# Sheet1.net
KiCad netlist of a schematic drawn in Altium Designer
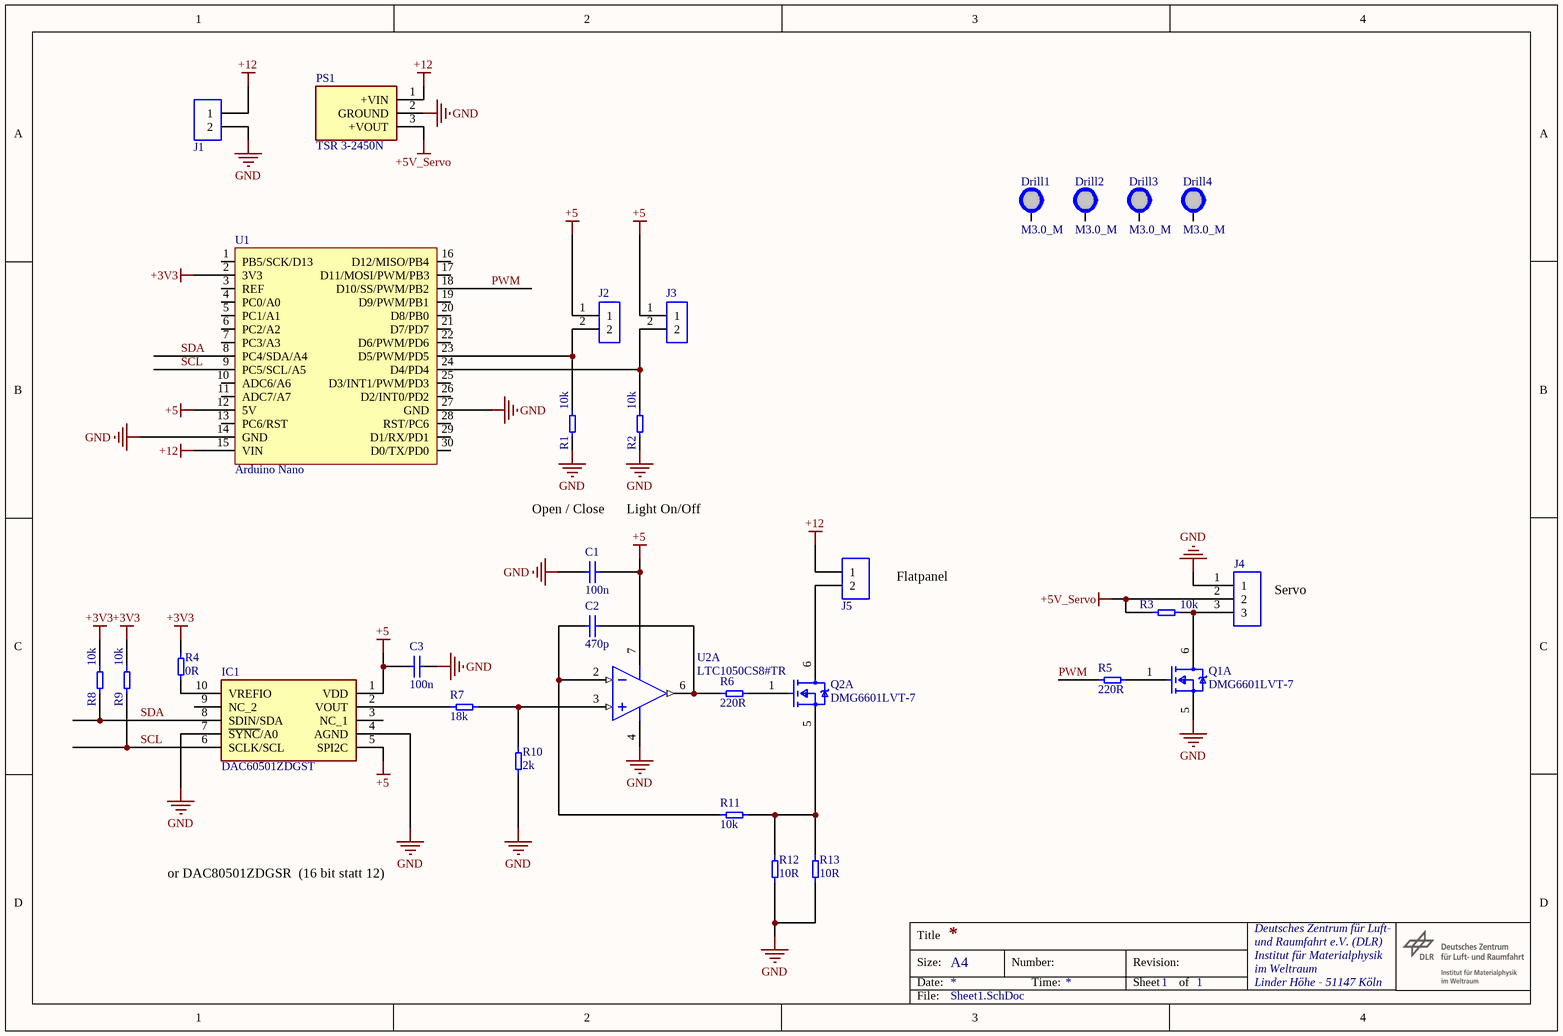
[diagram p0: Sheet1.SchDoc]

(export (version "E")
  (design (tool "Eeschema 10.0.6"))
  (components
    (comp (ref "C1")
      (value "100n")
      (footprint "C0603_L")
      (fields
        (field (name "PUBLISHER") "Altium Limited")
        (field (name ".CHECKED PCB") "RF")
        (field (name ".CHECKED SCH") "RF")
      )
      (libsource (lib "Passive Bauelemente") (part "C0603"))
    )
    (comp (ref "C2")
      (value "470p")
      (footprint "C0603_L")
      (fields
        (field (name "PUBLISHER") "Altium Limited")
        (field (name ".CHECKED PCB") "RF")
        (field (name ".CHECKED SCH") "RF")
      )
      (libsource (lib "Passive Bauelemente") (part "C0603"))
    )
    (comp (ref "C3")
      (value "100n")
      (footprint "C0603_L")
      (fields
        (field (name "PUBLISHER") "Altium Limited")
        (field (name ".CHECKED PCB") "RF")
        (field (name ".CHECKED SCH") "RF")
      )
      (libsource (lib "Passive Bauelemente") (part "C0603"))
    )
    (comp (ref "Drill1")
      (value "M3.0_M")
      (footprint "M3.0_M")
      (fields (field (name ".CHECKED PCB") "RF") (field (name ".CHECKED SCH") "RF"))
      (libsource (lib "Drills") (part "Drill"))
    )
    (comp (ref "Drill2")
      (value "M3.0_M")
      (footprint "M3.0_M")
      (fields (field (name ".CHECKED PCB") "RF") (field (name ".CHECKED SCH") "RF"))
      (libsource (lib "Drills") (part "Drill"))
    )
    (comp (ref "Drill3")
      (value "M3.0_M")
      (footprint "M3.0_M")
      (fields (field (name ".CHECKED PCB") "RF") (field (name ".CHECKED SCH") "RF"))
      (libsource (lib "Drills") (part "Drill"))
    )
    (comp (ref "Drill4")
      (value "M3.0_M")
      (footprint "M3.0_M")
      (fields (field (name ".CHECKED PCB") "RF") (field (name ".CHECKED SCH") "RF"))
      (libsource (lib "Drills") (part "Drill"))
    )
    (comp (ref "IC1")
      (value "DAC60501ZDGST")
      (footprint "SamacSys:SOP50P490X110-10N")
      (description "Integrated Circuit")
      (fields (field (name "MOUSER PART NUMBER") "595-DAC60501ZDGST"))
      (libsource (lib "*") (part "DAC60501ZDGST"))
    )
    (comp (ref "J1")
      (value "PM_5.08_3_90_3.5_SW_-176052000")
      (footprint "MKDSN 5,08/2 2,5")
      (description "间距5.08mm 2pin 10A 300V 可拼接 螺钉式 直插 配线24-14AWG(0.2-2.5)mm²")
      (fields
        (field (name "MANUFACTURER") "Phoenix Contact")
        (field (name "MANUFACTURER PART NUMBER") "1888687")
        (field (name ".CHECKED PCB") "PS")
        (field (name ".CHECKED SCH") "PS")
      )
      (libsource (lib "Phoenix Contact") (part "MKDSN 5,08/2 2,5"))
    )
    (comp (ref "J2")
      (value "896-7620")
      (footprint "2P Stiftleiste 2,54 mm")
      (fields
        (field (name "MANUFACTURER_PART_NUMBER") "42375-0002")
        (field (name ".CHECKED PCB") "RF")
        (field (name ".CHECKED SCH") "RF")
      )
      (libsource (lib "EigenDefault") (part "2P Stiftleiste 2,54"))
    )
    (comp (ref "J3")
      (value "896-7620")
      (footprint "2P Stiftleiste 2,54 mm")
      (fields
        (field (name "MANUFACTURER_PART_NUMBER") "42375-0002")
        (field (name ".CHECKED PCB") "RF")
        (field (name ".CHECKED SCH") "RF")
      )
      (libsource (lib "EigenDefault") (part "2P Stiftleiste 2,54"))
    )
    (comp (ref "J4")
      (value "251-8092")
      (footprint "3P Stiftleiste 2,54 mm")
      (fields (field (name ".CHECKED PCB") "RF") (field (name ".CHECKED SCH") "RF"))
      (libsource (lib "EigenDefault") (part "3P Stiftleiste 2,54"))
    )
    (comp (ref "J5")
      (value "PM_5.08_3_90_3.5_SW_-176052000")
      (footprint "MKDSN 5,08/2 2,5")
      (description "间距5.08mm 2pin 10A 300V 可拼接 螺钉式 直插 配线24-14AWG(0.2-2.5)mm²")
      (fields
        (field (name "MANUFACTURER") "Phoenix Contact")
        (field (name "MANUFACTURER PART NUMBER") "1888687")
        (field (name ".CHECKED PCB") "PS")
        (field (name ".CHECKED SCH") "PS")
      )
      (libsource (lib "Phoenix Contact") (part "MKDSN 5,08/2 2,5"))
    )
    (comp (ref "PS1")
      (value "TSR 3-2450N")
      (footprint "SamacSys:TSR324120N")
      (description "or TSR 3-2450N")
      (libsource (lib "*") (part "TSR_3-24120N"))
    )
    (comp (ref "Q1")
      (value "DMG6601LVT-7")
      (footprint "FP-TSOT26-MFG")
      (description "MOSFET N/P-CH 30V 26TSOT")
      (fields
        (field (name "OCTOPART") "https://octopart.com/dmg6601lvt-7-diodes+inc.-24548281")
        (field (name "MANUFACTURER") "Diodes Inc.")
      )
      (libsource (lib "Altium Content Vault") (part "06fe37a93ab8884fb11e636f76dd7e0"))
    )
    (comp (ref "Q2")
      (value "DMG6601LVT-7")
      (footprint "FP-TSOT26-MFG")
      (description "MOSFET N/P-CH 30V 26TSOT")
      (fields
        (field (name "OCTOPART") "https://octopart.com/dmg6601lvt-7-diodes+inc.-24548281")
        (field (name "MANUFACTURER") "Diodes Inc.")
      )
      (libsource (lib "Altium Content Vault") (part "06fe37a93ab8884fb11e636f76dd7e0"))
    )
    (comp (ref "R1")
      (value "10k")
      (footprint "R0603_M")
      (fields
        (field (name "POWER") "35 W")
        (field (name "PUBLISHER") "Altium Limited")
        (field (name ".CHECKED PCB") "RF")
        (field (name ".CHECKED SCH") "RF")
      )
      (libsource (lib "Passive Bauelemente") (part "R0603"))
    )
    (comp (ref "R2")
      (value "10k")
      (footprint "R0603_M")
      (fields
        (field (name "POWER") "35 W")
        (field (name "PUBLISHER") "Altium Limited")
        (field (name ".CHECKED PCB") "RF")
        (field (name ".CHECKED SCH") "RF")
      )
      (libsource (lib "Passive Bauelemente") (part "R0603"))
    )
    (comp (ref "R3")
      (value "10k")
      (footprint "R0603_M")
      (fields
        (field (name "POWER") "35 W")
        (field (name "PUBLISHER") "Altium Limited")
        (field (name ".CHECKED PCB") "RF")
        (field (name ".CHECKED SCH") "RF")
      )
      (libsource (lib "Passive Bauelemente") (part "R0603"))
    )
    (comp (ref "R4")
      (value "0R")
      (footprint "R0603_M")
      (fields
        (field (name "POWER") "35 W")
        (field (name "PUBLISHER") "Altium Limited")
        (field (name ".CHECKED PCB") "RF")
        (field (name ".CHECKED SCH") "RF")
      )
      (libsource (lib "Passive Bauelemente") (part "R0603"))
    )
    (comp (ref "R5")
      (value "220R")
      (footprint "R0603_M")
      (fields
        (field (name "POWER") "35 W")
        (field (name "PUBLISHER") "Altium Limited")
        (field (name ".CHECKED PCB") "RF")
        (field (name ".CHECKED SCH") "RF")
      )
      (libsource (lib "Passive Bauelemente") (part "R0603"))
    )
    (comp (ref "R6")
      (value "220R")
      (footprint "R0603_M")
      (fields
        (field (name "POWER") "35 W")
        (field (name "PUBLISHER") "Altium Limited")
        (field (name ".CHECKED PCB") "RF")
        (field (name ".CHECKED SCH") "RF")
      )
      (libsource (lib "Passive Bauelemente") (part "R0603"))
    )
    (comp (ref "R7")
      (value "18k")
      (footprint "R0603_M")
      (fields
        (field (name "POWER") "35 W")
        (field (name "PUBLISHER") "Altium Limited")
        (field (name ".CHECKED PCB") "RF")
        (field (name ".CHECKED SCH") "RF")
      )
      (libsource (lib "Passive Bauelemente") (part "R0603"))
    )
    (comp (ref "R8")
      (value "10k")
      (footprint "R0603_M")
      (fields
        (field (name "POWER") "35 W")
        (field (name "PUBLISHER") "Altium Limited")
        (field (name ".CHECKED PCB") "RF")
        (field (name ".CHECKED SCH") "RF")
      )
      (libsource (lib "Passive Bauelemente") (part "R0603"))
    )
    (comp (ref "R9")
      (value "10k")
      (footprint "R0603_M")
      (fields
        (field (name "POWER") "35 W")
        (field (name "PUBLISHER") "Altium Limited")
        (field (name ".CHECKED PCB") "RF")
        (field (name ".CHECKED SCH") "RF")
      )
      (libsource (lib "Passive Bauelemente") (part "R0603"))
    )
    (comp (ref "R10")
      (value "2k")
      (footprint "R0603_M")
      (fields
        (field (name "POWER") "35 W")
        (field (name "PUBLISHER") "Altium Limited")
        (field (name ".CHECKED PCB") "RF")
        (field (name ".CHECKED SCH") "RF")
      )
      (libsource (lib "Passive Bauelemente") (part "R0603"))
    )
    (comp (ref "R11")
      (value "10k")
      (footprint "R0603_M")
      (fields
        (field (name "POWER") "35 W")
        (field (name "PUBLISHER") "Altium Limited")
        (field (name ".CHECKED PCB") "RF")
        (field (name ".CHECKED SCH") "RF")
      )
      (libsource (lib "Passive Bauelemente") (part "R0603"))
    )
    (comp (ref "R12")
      (value "10R")
      (footprint "R0805_M")
      (fields
        (field (name "POWER") "35 W")
        (field (name "PUBLISHER") "Altium Limited")
        (field (name ".CHECKED PCB") "RF")
        (field (name ".CHECKED SCH") "RF")
      )
      (libsource (lib "Passive Bauelemente") (part "R0805"))
    )
    (comp (ref "R13")
      (value "10R")
      (footprint "R0805_M")
      (fields
        (field (name "POWER") "35 W")
        (field (name "PUBLISHER") "Altium Limited")
        (field (name ".CHECKED PCB") "RF")
        (field (name ".CHECKED SCH") "RF")
      )
      (libsource (lib "Passive Bauelemente") (part "R0805"))
    )
    (comp (ref "U1")
      (value "Arduino Nano")
      (footprint "Arduino Nano")
      (description "Nano Every Development Brd, 8Bit Avr Mcu Rohs Compliant: Yes")
      (fields
        (field (name "MANUFACTURER") "Arduino")
        (field (name "MANUFACTURER PART NUMBER") "ABX00028")
        (field (name ".SCH CHECKED") "PS")
        (field (name ".PCB CHECKED") "PS")
      )
      (libsource (lib "Arduino System") (part "Arduino Nano"))
    )
    (comp (ref "U2")
      (value "LTC1050CS8#TR")
      (footprint "LT-S8-8_L")
      (fields
        (field (name "MANUFACTURER") "Linear Technology")
        (field (name "LINEAR TECHNOLOGY PART NUMBER") "LTC1050")
      )
      (libsource (lib "Altium Content Vault") (part "LT-LTC1050-8"))
    )
  )
  (nets
    (net (code "1") (name "+3V3") (class "Default")
      (node (ref "R4") (pin "1") (pinfunction "1_1") (pintype "passive"))
      (node (ref "R8") (pin "1") (pinfunction "1_1") (pintype "passive"))
      (node (ref "R9") (pin "1") (pinfunction "1_1") (pintype "passive"))
      (node (ref "U1") (pin "2") (pinfunction "3V3_2") (pintype "passive"))
    )
    (net (code "2") (name "+5") (class "Default")
      (node (ref "C1") (pin "1") (pinfunction "1_1") (pintype "passive"))
      (node (ref "C3") (pin "1") (pinfunction "1_1") (pintype "passive"))
      (node (ref "IC1") (pin "1") (pinfunction "VDD_1") (pintype "passive"))
      (node (ref "IC1") (pin "5") (pinfunction "SPI2C_5") (pintype "passive"))
      (node (ref "J2") (pin "1") (pinfunction "1_1") (pintype "passive"))
      (node (ref "J3") (pin "1") (pinfunction "1_1") (pintype "passive"))
      (node (ref "U1") (pin "12") (pinfunction "5V_12") (pintype "passive"))
      (node (ref "U2") (pin "7") (pinfunction "V+_7") (pintype "power_in"))
    )
    (net (code "3") (name "+5V_Servo") (class "Default")
      (node (ref "J4") (pin "2") (pinfunction "2_2") (pintype "passive"))
      (node (ref "PS1") (pin "3") (pinfunction "+VOUT_3") (pintype "passive"))
      (node (ref "R3") (pin "1") (pinfunction "1_1") (pintype "passive"))
    )
    (net (code "4") (name "+12") (class "Default")
      (node (ref "J1") (pin "1") (pinfunction "1_1") (pintype "passive"))
      (node (ref "J5") (pin "1") (pinfunction "1_1") (pintype "passive"))
      (node (ref "PS1") (pin "1") (pinfunction "+VIN_1") (pintype "passive"))
      (node (ref "U1") (pin "15") (pinfunction "VIN_15") (pintype "passive"))
    )
    (net (code "5") (name "/PWM") (class "Default")
      (node (ref "R5") (pin "1") (pinfunction "1_1") (pintype "passive"))
      (node (ref "U1") (pin "18") (pinfunction "D10/SS/PWM/PB2_18") (pintype "passive"))
    )
    (net (code "6") (name "/SCL") (class "Default")
      (node (ref "IC1") (pin "6") (pinfunction "SCLK/SCL_6") (pintype "passive"))
      (node (ref "R9") (pin "2") (pinfunction "2_2") (pintype "passive"))
      (node (ref "U1") (pin "9") (pinfunction "PC5/SCL/A5_9") (pintype "passive"))
    )
    (net (code "7") (name "/SDA") (class "Default")
      (node (ref "IC1") (pin "8") (pinfunction "SDIN/SDA_8") (pintype "passive"))
      (node (ref "R8") (pin "2") (pinfunction "2_2") (pintype "passive"))
      (node (ref "U1") (pin "8") (pinfunction "PC4/SDA/A4_8") (pintype "passive"))
    )
    (net (code "8") (name "GND") (class "Default")
      (node (ref "C1") (pin "2") (pinfunction "2_2") (pintype "passive"))
      (node (ref "C3") (pin "2") (pinfunction "2_2") (pintype "passive"))
      (node (ref "IC1") (pin "4") (pinfunction "AGND_4") (pintype "passive"))
      (node (ref "IC1") (pin "7") (pinfunction "~{SYNC}/A0_7") (pintype "passive"))
      (node (ref "J1") (pin "2") (pinfunction "2_2") (pintype "passive"))
      (node (ref "J4") (pin "1") (pinfunction "1_1") (pintype "passive"))
      (node (ref "PS1") (pin "2") (pinfunction "GROUND_2") (pintype "passive"))
      (node (ref "Q1") (pin "5") (pinfunction "S1_5") (pintype "passive"))
      (node (ref "R1") (pin "2") (pinfunction "2_2") (pintype "passive"))
      (node (ref "R10") (pin "1") (pinfunction "1_1") (pintype "passive"))
      (node (ref "R12") (pin "1") (pinfunction "1_1") (pintype "passive"))
      (node (ref "R13") (pin "1") (pinfunction "1_1") (pintype "passive"))
      (node (ref "R2") (pin "2") (pinfunction "2_2") (pintype "passive"))
      (node (ref "U1") (pin "14") (pinfunction "GND_14") (pintype "passive"))
      (node (ref "U1") (pin "27") (pinfunction "GND_27") (pintype "passive"))
      (node (ref "U2") (pin "4") (pinfunction "V-_4") (pintype "power_in"))
    )
    (net (code "9") (name "Net-(IC1-VOUT)") (class "Default")
      (node (ref "IC1") (pin "2") (pinfunction "VOUT_2") (pintype "passive"))
      (node (ref "R7") (pin "1") (pinfunction "1_1") (pintype "passive"))
    )
    (net (code "10") (name "Net-(IC1-VREFIO)") (class "Default")
      (node (ref "IC1") (pin "10") (pinfunction "VREFIO_10") (pintype "passive"))
      (node (ref "R4") (pin "2") (pinfunction "2_2") (pintype "passive"))
    )
    (net (code "11") (name "Net-(Q1A-D1)") (class "Default")
      (node (ref "J4") (pin "3") (pinfunction "3_3") (pintype "passive"))
      (node (ref "Q1") (pin "6") (pinfunction "D1_6") (pintype "passive"))
      (node (ref "R3") (pin "2") (pinfunction "2_2") (pintype "passive"))
    )
    (net (code "12") (name "Net-(Q1A-G1)") (class "Default")
      (node (ref "Q1") (pin "1") (pinfunction "G1_1") (pintype "passive"))
      (node (ref "R5") (pin "2") (pinfunction "2_2") (pintype "passive"))
    )
    (net (code "13") (name "Net-(Q2A-D1)") (class "Default")
      (node (ref "J5") (pin "2") (pinfunction "2_2") (pintype "passive"))
      (node (ref "Q2") (pin "6") (pinfunction "D1_6") (pintype "passive"))
    )
    (net (code "14") (name "Net-(Q2A-G1)") (class "Default")
      (node (ref "Q2") (pin "1") (pinfunction "G1_1") (pintype "passive"))
      (node (ref "R6") (pin "2") (pinfunction "2_2") (pintype "passive"))
    )
    (net (code "15") (name "Net-(Q2A-S1)") (class "Default")
      (node (ref "Q2") (pin "5") (pinfunction "S1_5") (pintype "passive"))
      (node (ref "R11") (pin "2") (pinfunction "2_2") (pintype "passive"))
      (node (ref "R12") (pin "2") (pinfunction "2_2") (pintype "passive"))
      (node (ref "R13") (pin "2") (pinfunction "2_2") (pintype "passive"))
    )
    (net (code "16") (name "Net-(U1-D4{slash}PD4)") (class "Default")
      (node (ref "J3") (pin "2") (pinfunction "2_2") (pintype "passive"))
      (node (ref "R2") (pin "1") (pinfunction "1_1") (pintype "passive"))
      (node (ref "U1") (pin "24") (pinfunction "D4/PD4_24") (pintype "passive"))
    )
    (net (code "17") (name "Net-(U1-D5{slash}PWM{slash}PD5)") (class "Default")
      (node (ref "J2") (pin "2") (pinfunction "2_2") (pintype "passive"))
      (node (ref "R1") (pin "1") (pinfunction "1_1") (pintype "passive"))
      (node (ref "U1") (pin "23") (pinfunction "D5/PWM/PD5_23") (pintype "passive"))
    )
    (net (code "18") (name "Net-(U2A-+IN)") (class "Default")
      (node (ref "R10") (pin "2") (pinfunction "2_2") (pintype "passive"))
      (node (ref "R7") (pin "2") (pinfunction "2_2") (pintype "passive"))
      (node (ref "U2") (pin "3") (pinfunction "+IN_3") (pintype "input"))
    )
    (net (code "19") (name "Net-(U2A--IN)") (class "Default")
      (node (ref "C2") (pin "1") (pinfunction "1_1") (pintype "passive"))
      (node (ref "R11") (pin "1") (pinfunction "1_1") (pintype "passive"))
      (node (ref "U2") (pin "2") (pinfunction "-IN_2") (pintype "input"))
    )
    (net (code "20") (name "Net-(U2A-OUT)") (class "Default")
      (node (ref "C2") (pin "2") (pinfunction "2_2") (pintype "passive"))
      (node (ref "R6") (pin "1") (pinfunction "1_1") (pintype "passive"))
      (node (ref "U2") (pin "6") (pinfunction "OUT_6") (pintype "output"))
    )
    (net (code "21") (name "unconnected-(Drill1-Pad1)") (class "Default")
      (node (ref "Drill1") (pin "1") (pinfunction "1_1") (pintype "passive"))
    )
    (net (code "22") (name "unconnected-(Drill2-Pad1)") (class "Default")
      (node (ref "Drill2") (pin "1") (pinfunction "1_1") (pintype "passive"))
    )
    (net (code "23") (name "unconnected-(Drill3-Pad1)") (class "Default")
      (node (ref "Drill3") (pin "1") (pinfunction "1_1") (pintype "passive"))
    )
    (net (code "24") (name "unconnected-(Drill4-Pad1)") (class "Default")
      (node (ref "Drill4") (pin "1") (pinfunction "1_1") (pintype "passive"))
    )
    (net (code "25") (name "unconnected-(IC1-NC_1-Pad3)") (class "Default")
      (node (ref "IC1") (pin "3") (pinfunction "NC_1_3") (pintype "passive"))
    )
    (net (code "26") (name "unconnected-(IC1-NC_2-Pad9)") (class "Default")
      (node (ref "IC1") (pin "9") (pinfunction "NC_2_9") (pintype "passive"))
    )
    (net (code "27") (name "unconnected-(U1-ADC6{slash}A6-Pad10)") (class "Default")
      (node (ref "U1") (pin "10") (pinfunction "ADC6/A6_10") (pintype "passive"))
    )
    (net (code "28") (name "unconnected-(U1-ADC7{slash}A7-Pad11)") (class "Default")
      (node (ref "U1") (pin "11") (pinfunction "ADC7/A7_11") (pintype "passive"))
    )
    (net (code "29") (name "unconnected-(U1-D0{slash}TX{slash}PD0-Pad30)") (class "Default")
      (node (ref "U1") (pin "30") (pinfunction "D0/TX/PD0_30") (pintype "passive"))
    )
    (net (code "30") (name "unconnected-(U1-D1{slash}RX{slash}PD1-Pad29)") (class "Default")
      (node (ref "U1") (pin "29") (pinfunction "D1/RX/PD1_29") (pintype "passive"))
    )
    (net (code "31") (name "unconnected-(U1-D2{slash}INT0{slash}PD2-Pad26)") (class "Default")
      (node (ref "U1") (pin "26") (pinfunction "D2/INT0/PD2_26") (pintype "passive"))
    )
    (net (code "32") (name "unconnected-(U1-D3{slash}INT1{slash}PWM{slash}PD3-Pad25)") (class "Default")
      (node (ref "U1") (pin "25") (pinfunction "D3/INT1/PWM/PD3_25") (pintype "passive"))
    )
    (net (code "33") (name "unconnected-(U1-D6{slash}PWM{slash}PD6-Pad22)") (class "Default")
      (node (ref "U1") (pin "22") (pinfunction "D6/PWM/PD6_22") (pintype "passive"))
    )
    (net (code "34") (name "unconnected-(U1-D7{slash}PD7-Pad21)") (class "Default")
      (node (ref "U1") (pin "21") (pinfunction "D7/PD7_21") (pintype "passive"))
    )
    (net (code "35") (name "unconnected-(U1-D8{slash}PB0-Pad20)") (class "Default")
      (node (ref "U1") (pin "20") (pinfunction "D8/PB0_20") (pintype "passive"))
    )
    (net (code "36") (name "unconnected-(U1-D9{slash}PWM{slash}PB1-Pad19)") (class "Default")
      (node (ref "U1") (pin "19") (pinfunction "D9/PWM/PB1_19") (pintype "passive"))
    )
    (net (code "37") (name "unconnected-(U1-D11{slash}MOSI{slash}PWM{slash}PB3-Pad17)") (class "Default")
      (node (ref "U1") (pin "17") (pinfunction "D11/MOSI/PWM/PB3_17") (pintype "passive"))
    )
    (net (code "38") (name "unconnected-(U1-D12{slash}MISO{slash}PB4-Pad16)") (class "Default")
      (node (ref "U1") (pin "16") (pinfunction "D12/MISO/PB4_16") (pintype "passive"))
    )
    (net (code "39") (name "unconnected-(U1-PB5{slash}SCK{slash}D13-Pad1)") (class "Default")
      (node (ref "U1") (pin "1") (pinfunction "PB5/SCK/D13_1") (pintype "passive"))
    )
    (net (code "40") (name "unconnected-(U1-PC0{slash}A0-Pad4)") (class "Default")
      (node (ref "U1") (pin "4") (pinfunction "PC0/A0_4") (pintype "passive"))
    )
    (net (code "41") (name "unconnected-(U1-PC1{slash}A1-Pad5)") (class "Default")
      (node (ref "U1") (pin "5") (pinfunction "PC1/A1_5") (pintype "passive"))
    )
    (net (code "42") (name "unconnected-(U1-PC2{slash}A2-Pad6)") (class "Default")
      (node (ref "U1") (pin "6") (pinfunction "PC2/A2_6") (pintype "passive"))
    )
    (net (code "43") (name "unconnected-(U1-PC3{slash}A3-Pad7)") (class "Default")
      (node (ref "U1") (pin "7") (pinfunction "PC3/A3_7") (pintype "passive"))
    )
    (net (code "44") (name "unconnected-(U1-PC6{slash}RST-Pad13)") (class "Default")
      (node (ref "U1") (pin "13") (pinfunction "PC6/RST_13") (pintype "passive"))
    )
    (net (code "45") (name "unconnected-(U1-REF-Pad3)") (class "Default")
      (node (ref "U1") (pin "3") (pinfunction "REF_3") (pintype "passive"))
    )
    (net (code "46") (name "unconnected-(U1-RST{slash}PC6-Pad28)") (class "Default")
      (node (ref "U1") (pin "28") (pinfunction "RST/PC6_28") (pintype "passive"))
    )
  )
)
